# Res_Adjustment.net
KiCad netlist of a schematic drawn in Altium Designer
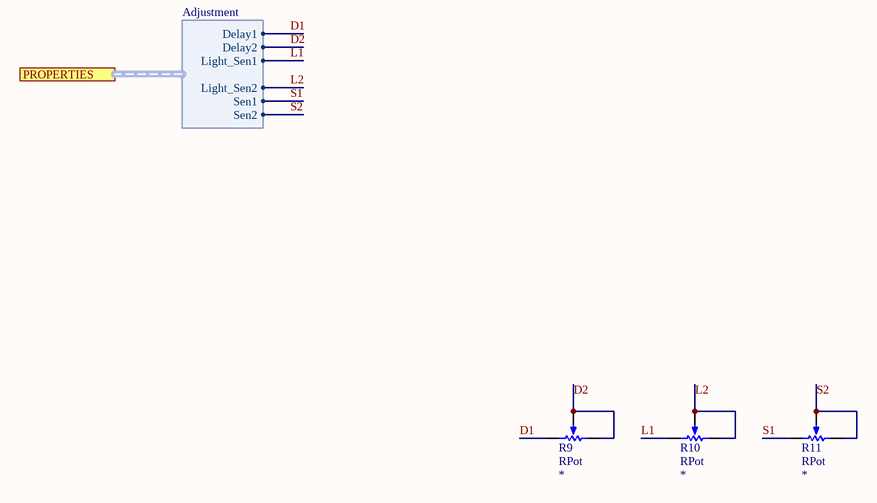
[diagram p0: Res_Adjustment.SchDoc]

(export (version "E")
  (design (tool "Eeschema 10.0.6"))
  (components
    (comp (ref "R9")
      (value "RPot")
      (footprint "VR3362P")
      (description "Potentiometer")
      (fields (field (name "RES") "*"))
      (libsource (lib "Schlib") (part "RPot"))
    )
    (comp (ref "R10")
      (value "RPot")
      (footprint "VR3362P")
      (description "Potentiometer")
      (fields (field (name "RES") "*"))
      (libsource (lib "Schlib") (part "RPot"))
    )
    (comp (ref "R11")
      (value "RPot")
      (footprint "VR3362P")
      (description "Potentiometer")
      (fields (field (name "RES") "*"))
      (libsource (lib "Schlib") (part "RPot"))
    )
  )
  (nets
    (net (code "2") (name "/D1") (class "Default")
      (node (ref "R9") (pin "3") (pinfunction "BOT_3") (pintype "passive"))
    )
    (net (code "3") (name "/D2") (class "Default")
      (node (ref "R9") (pin "1") (pinfunction "TOP_1") (pintype "passive"))
      (node (ref "R9") (pin "2") (pinfunction "TAP_2") (pintype "passive"))
    )
    (net (code "4") (name "/L1") (class "Default")
      (node (ref "R10") (pin "3") (pinfunction "BOT_3") (pintype "passive"))
    )
    (net (code "5") (name "/L2") (class "Default")
      (node (ref "R10") (pin "1") (pinfunction "TOP_1") (pintype "passive"))
      (node (ref "R10") (pin "2") (pinfunction "TAP_2") (pintype "passive"))
    )
    (net (code "6") (name "/S1") (class "Default")
      (node (ref "R11") (pin "3") (pinfunction "BOT_3") (pintype "passive"))
    )
    (net (code "7") (name "/S2") (class "Default")
      (node (ref "R11") (pin "1") (pinfunction "TOP_1") (pintype "passive"))
      (node (ref "R11") (pin "2") (pinfunction "TAP_2") (pintype "passive"))
    )
  )
)
